# PAGE1.net
KiCad netlist of a schematic drawn in Altium Designer
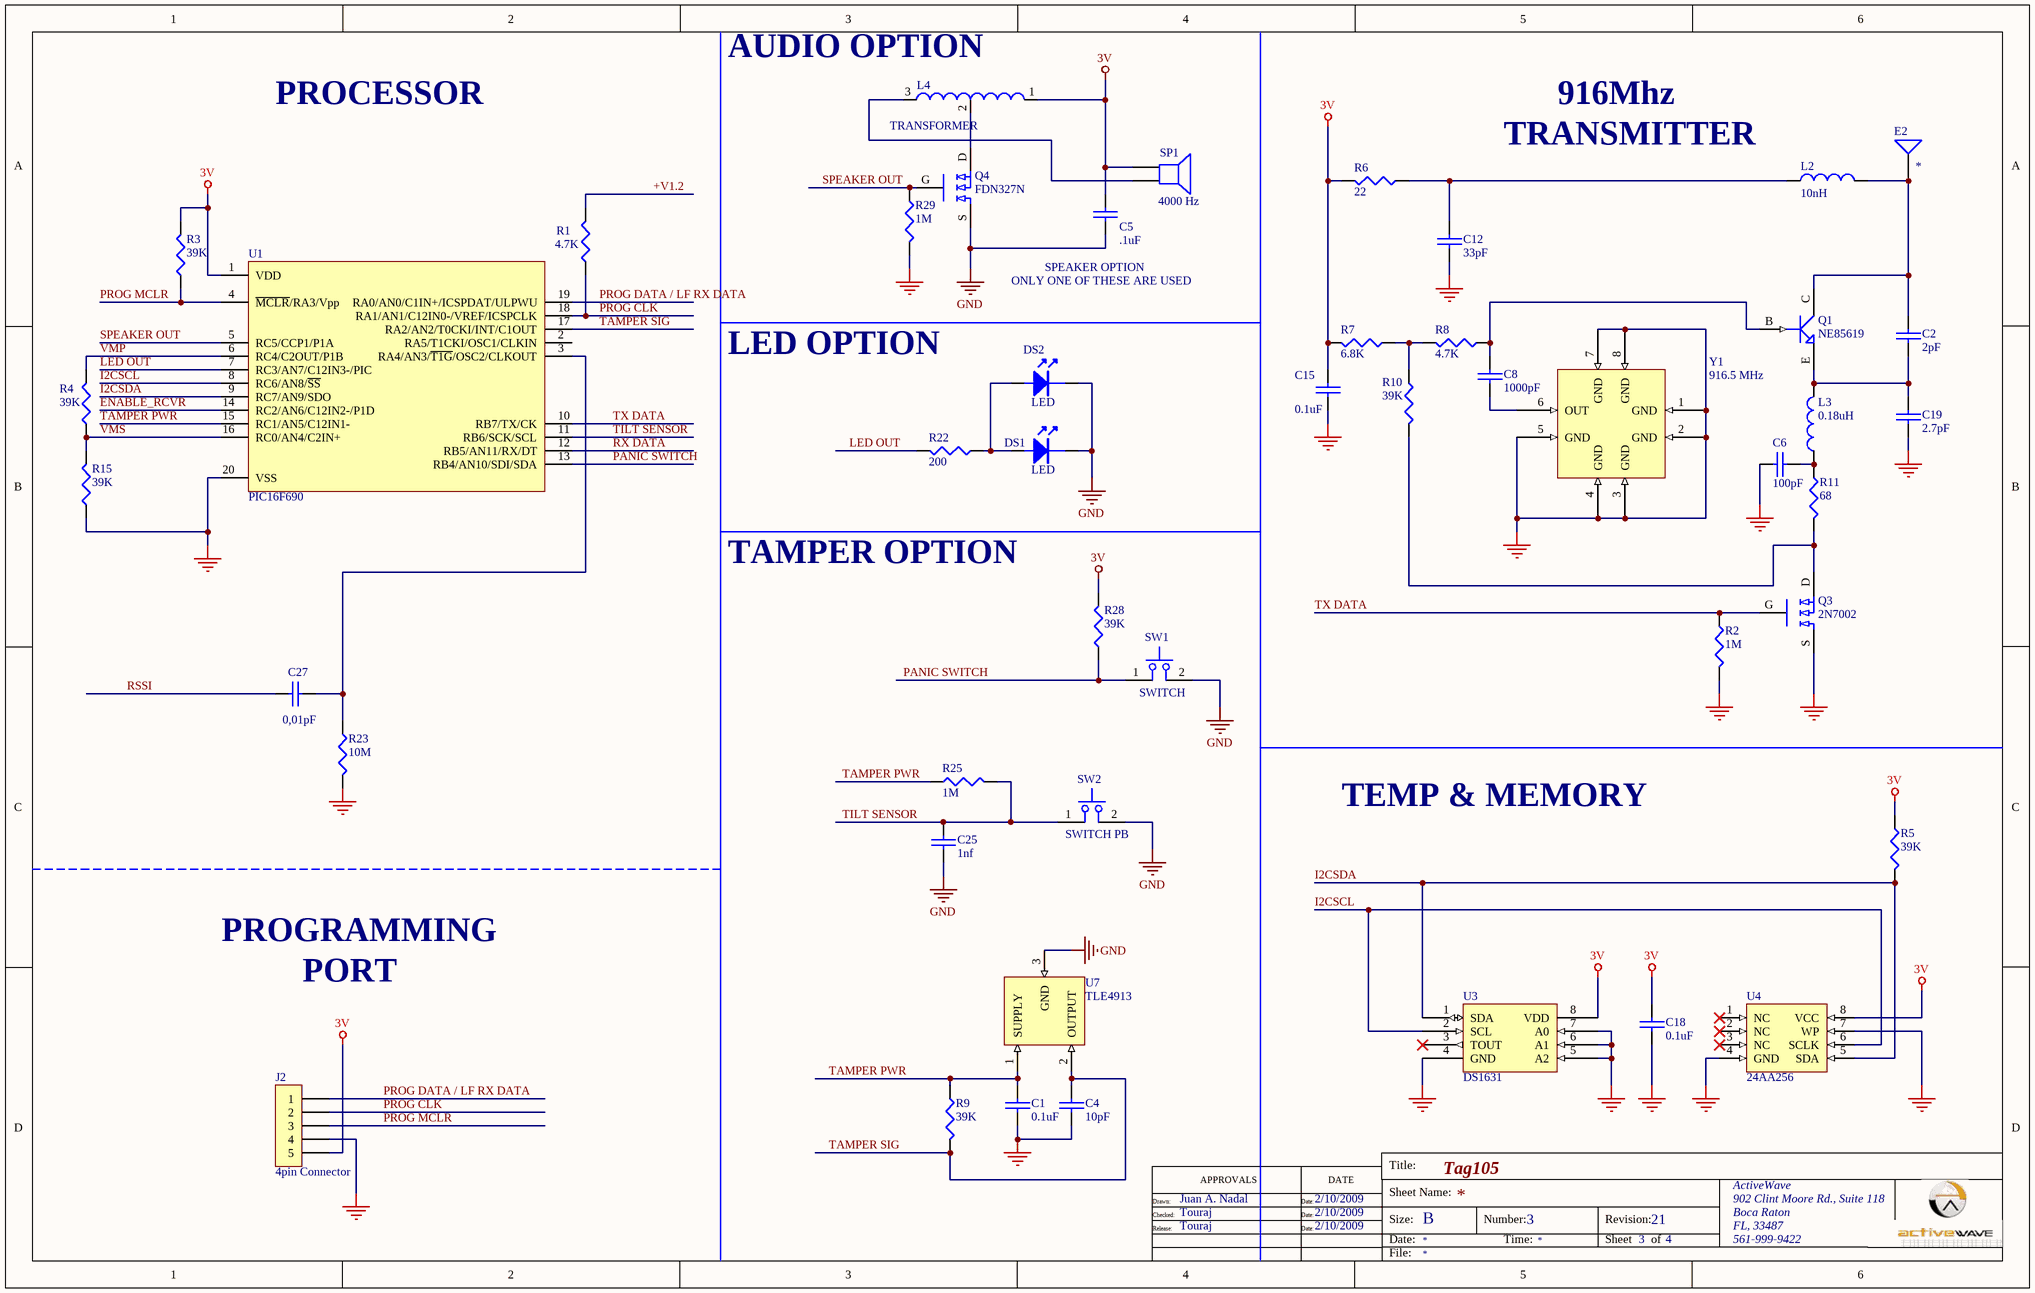
[diagram p0: PAGE1.schdoc]

(export (version "E")
  (design (tool "Eeschema 10.0.6"))
  (components
    (comp (ref "C1")
      (value "0.1uF")
      (footprint "0603")
      (description "Capacitor")
      (libsource (lib "ActiveWave MasterLib") (part "CAP-0603"))
    )
    (comp (ref "C2")
      (value "2pF")
      (footprint "0603")
      (description "Capacitor")
      (libsource (lib "ActiveWave MasterLib") (part "CAP-0603"))
    )
    (comp (ref "C4")
      (value "10pF")
      (footprint "0603")
      (description "Capacitor")
      (libsource (lib "ActiveWave MasterLib") (part "CAP-0603"))
    )
    (comp (ref "C5")
      (value ".1uF")
      (footprint "0603")
      (description "Capacitor")
      (libsource (lib "ActiveWave MasterLib") (part "CAP-0603"))
    )
    (comp (ref "C6")
      (value "100pF")
      (footprint "0603")
      (description "Capacitor")
      (libsource (lib "ActiveWave MasterLib") (part "CAP-0603"))
    )
    (comp (ref "C8")
      (value "1000pF")
      (footprint "0603")
      (description "Capacitor")
      (libsource (lib "ActiveWave MasterLib") (part "CAP-0603"))
    )
    (comp (ref "C12")
      (value "33pF")
      (footprint "0603")
      (description "Capacitor")
      (libsource (lib "ActiveWave MasterLib") (part "CAP-0603"))
    )
    (comp (ref "C15")
      (value "0.1uF")
      (footprint "0603")
      (description "Capacitor")
      (libsource (lib "ActiveWave MasterLib") (part "CAP-0603"))
    )
    (comp (ref "C18")
      (value "0.1uF")
      (footprint "0603")
      (description "Capacitor")
      (libsource (lib "ActiveWave MasterLib") (part "CAP-0603"))
    )
    (comp (ref "C19")
      (value "2.7pF")
      (footprint "0603")
      (description "Capacitor")
      (libsource (lib "ActiveWave MasterLib") (part "CAP-0603"))
    )
    (comp (ref "C25")
      (value "1nf")
      (footprint "0603")
      (description "Capacitor")
      (libsource (lib "ActiveWave MasterLib") (part "CAP-0603"))
    )
    (comp (ref "C27")
      (value "0,01pF")
      (footprint "0603")
      (description "Capacitor")
      (libsource (lib "ActiveWave MasterLib") (part "CAP-0603"))
    )
    (comp (ref "DS1")
      (value "LED")
      (footprint "404-1032-2-ND")
      (libsource (lib "ActiveWave MasterLib") (part "LED"))
    )
    (comp (ref "DS2")
      (value "LED")
      (footprint "LCE-358RP")
      (description "X-Bring Red Power SMD LED Emitter")
      (fields (field (name "MANUFACTURER") "L.C. LED"))
      (libsource (lib "ActiveWave MasterLib") (part "LCE-358RP"))
    )
    (comp (ref "E2")
      (value "*")
      (footprint "Antenna1")
      (fields (field (name "ALTIUM_VALUE") "*"))
      (libsource (lib "ActiveWave MasterLib") (part "Antenna1"))
    )
    (comp (ref "J2")
      (value "4pin Connector")
      (footprint "1X5 HEADER")
      (description "Connector")
      (libsource (lib "ActiveWave MasterLib") (part "CON5-1"))
    )
    (comp (ref "L2")
      (value "10nH")
      (footprint "0603")
      (libsource (lib "ActiveWave MasterLib") (part "INDUCTOR"))
    )
    (comp (ref "L3")
      (value "0.18uH")
      (footprint "0603")
      (libsource (lib "ActiveWave MasterLib") (part "INDUCTOR"))
    )
    (comp (ref "L4")
      (value "TRANSFORMER")
      (footprint "COIL_6mmx6mm_011012")
      (libsource (lib "ActiveWave MasterLib") (part "INDUCTOR_V2"))
    )
    (comp (ref "Q1")
      (value "NE85619")
      (footprint "3 PIN ULTRA SUPER MINI MOLD")
      (description "TRANSISTOR NPN 1GHZ SMD")
      (fields (field (name "MANUFACTURER") "??????"))
      (libsource (lib "ActiveWave MasterLib") (part "NE85619"))
    )
    (comp (ref "Q3")
      (value "2N7002")
      (footprint "SOT23 FET")
      (description "N-CHANNEL ENHANCEMENT MODE FIELD EFFECT TRANSISTOR")
      (fields (field (name "MANUFACTURER") "FAIRCHILD"))
      (libsource (lib "ActiveWave MasterLib") (part "2N7002"))
    )
    (comp (ref "Q4")
      (value "FDN327N")
      (footprint "SOT23 FET")
      (description "20V N-Channel MOSFET")
      (fields (field (name "MANUFACTURER") "FAIRCHILD"))
      (libsource (lib "ActiveWave MasterLib") (part "FDN327N"))
    )
    (comp (ref "R1") (value "4.7K") (footprint "0603") (libsource (lib "*") (part "RESISTOR")))
    (comp (ref "R2") (value "1M") (libsource (lib "ActiveWave MasterLib") (part "RES-0402")))
    (comp (ref "R3")
      (value "39K")
      (footprint "0603")
      (libsource (lib "ActiveWave MasterLib") (part "RES-0603"))
    )
    (comp (ref "R4")
      (value "39K")
      (footprint "0603")
      (libsource (lib "ActiveWave MasterLib") (part "RES-0603"))
    )
    (comp (ref "R5")
      (value "39K")
      (footprint "0603")
      (libsource (lib "ActiveWave MasterLib") (part "RES-0603"))
    )
    (comp (ref "R6") (value "22") (libsource (lib "ActiveWave MasterLib") (part "RES-0402")))
    (comp (ref "R7") (value "6.8K") (libsource (lib "ActiveWave MasterLib") (part "RES-0402")))
    (comp (ref "R8") (value "4.7K") (libsource (lib "ActiveWave MasterLib") (part "RES-0402")))
    (comp (ref "R9")
      (value "39K")
      (footprint "0603")
      (libsource (lib "ActiveWave MasterLib") (part "RES-0603"))
    )
    (comp (ref "R10")
      (value "39K")
      (footprint "0603")
      (libsource (lib "ActiveWave MasterLib") (part "RES-0603"))
    )
    (comp (ref "R11") (value "68") (libsource (lib "ActiveWave MasterLib") (part "RES-0402")))
    (comp (ref "R15")
      (value "39K")
      (footprint "0603")
      (libsource (lib "ActiveWave MasterLib") (part "RES-0603"))
    )
    (comp (ref "R22")
      (value "200")
      (footprint "0603")
      (libsource (lib "ActiveWave MasterLib") (part "RES-0603"))
    )
    (comp (ref "R23")
      (value "10M")
      (footprint "0603")
      (libsource (lib "ActiveWave MasterLib") (part "RES-0603"))
    )
    (comp (ref "R25")
      (value "1M")
      (footprint "0603")
      (libsource (lib "ActiveWave MasterLib") (part "RES-0603"))
    )
    (comp (ref "R28")
      (value "39K")
      (footprint "0603")
      (libsource (lib "ActiveWave MasterLib") (part "RES-0603"))
    )
    (comp (ref "R29")
      (value "1M")
      (footprint "0603")
      (libsource (lib "ActiveWave MasterLib") (part "RES-0402"))
    )
    (comp (ref "SP1")
      (value "4000 Hz")
      (footprint "SPEAKER 12mmx12mm_011012")
      (description "Surface Mount Transducer")
      (fields (field (name "MANUFACTURER") "PUI Audio"))
      (libsource (lib "ActiveWave MasterLib") (part "SMT-1028-S-R"))
    )
    (comp (ref "SW1")
      (value "SWITCH")
      (footprint "SWITCH PB REVERSED_082907")
      (libsource (lib "ActiveWave MasterLib") (part "SWITCH"))
    )
    (comp (ref "SW2")
      (value "SWITCH PB")
      (footprint "SQ-SEN-DUAL1")
      (libsource (lib "ActiveWave MasterLib") (part "SWITCH PB"))
    )
    (comp (ref "U1")
      (value "PIC16F690")
      (footprint "SSOP20 WIDE")
      (description "Microcontrollers (MCU) 7KB FL 256R 18 I/O")
      (fields (field (name "MANUFACTURER") "Microchip"))
      (libsource (lib "ActiveWave MasterLib") (part "PIC16F690-E/P"))
    )
    (comp (ref "U3")
      (value "DS1631")
      (footprint "SO8 SMALL")
      (description "High-Precision Digital Thermometer and Thermostat")
      (fields (field (name "MANUFACTURER") "DALLAS SEMICONDUCTOR"))
      (libsource (lib "ActiveWave MasterLib") (part "DS1631"))
    )
    (comp (ref "U4")
      (value "24AA256")
      (footprint "SO8")
      (description "24AA256 32k Microchip Serial EEPROM")
      (fields (field (name "MANUFACTURER") "Microchip"))
      (libsource (lib "ActiveWave MasterLib") (part "24AA256-I/P"))
    )
    (comp (ref "U7")
      (value "TLE4913")
      (footprint "SOT23W")
      (description "Low Power Hall Switch")
      (fields (field (name "MANUFACTURER") "Infineon Technologies AG"))
      (libsource (lib "ActiveWave MasterLib") (part "TLE4913"))
    )
    (comp (ref "Y1")
      (value "916.5 MHz")
      (footprint "RESONATOR")
      (description "916.5 MHz Saw Resonator")
      (fields (field (name "MANUFACTURER") "??????"))
      (libsource (lib "ActiveWave MasterLib") (part "RESONATOR"))
    )
  )
  (nets
    (net (code "1") (name "/+V1.2") (class "Default")
      (node (ref "R1") (pin "2") (pinfunction "2_2") (pintype "passive"))
    )
    (net (code "2") (name "/ENABLE_RCVR") (class "Default")
      (node (ref "U1") (pin "14") (pinfunction "RC2/AN6/C12IN2-/P1D_14") (pintype "passive"))
    )
    (net (code "3") (name "/I2CSCL") (class "Default")
      (node (ref "U1") (pin "8") (pinfunction "RC6/AN8/~{SS}_8") (pintype "passive"))
      (node (ref "U3") (pin "2") (pinfunction "SCL_2") (pintype "input"))
      (node (ref "U4") (pin "6") (pinfunction "SCLK_6") (pintype "input"))
    )
    (net (code "4") (name "/I2CSDA") (class "Default")
      (node (ref "R5") (pin "2") (pinfunction "2_2") (pintype "passive"))
      (node (ref "U1") (pin "9") (pinfunction "RC7/AN9/SDO_9") (pintype "passive"))
      (node (ref "U3") (pin "1") (pinfunction "SDA_1") (pintype "bidirectional"))
      (node (ref "U4") (pin "5") (pinfunction "SDA_5") (pintype "input"))
    )
    (net (code "5") (name "/LED OUT") (class "Default")
      (node (ref "R22") (pin "2") (pinfunction "2_2") (pintype "passive"))
      (node (ref "U1") (pin "7") (pinfunction "RC3/AN7/C12IN3-/PIC_7") (pintype "passive"))
    )
    (net (code "6") (name "/PANIC SWITCH") (class "Default")
      (node (ref "R28") (pin "1") (pinfunction "1_1") (pintype "passive"))
      (node (ref "SW1") (pin "1") (pinfunction "1_1") (pintype "passive"))
      (node (ref "U1") (pin "13") (pinfunction "RB4/AN10/SDI/SDA_13") (pintype "passive"))
    )
    (net (code "7") (name "/PROG CLK") (class "Default")
      (node (ref "J2") (pin "2") (pinfunction "2_2") (pintype "passive"))
      (node (ref "R1") (pin "1") (pinfunction "1_1") (pintype "passive"))
      (node (ref "U1") (pin "18") (pinfunction "RA1/AN1/C12IN0-/VREF/ICSPCLK_18") (pintype "passive"))
    )
    (net (code "8") (name "/PROG DATA {slash} LF RX DATA") (class "Default")
      (node (ref "J2") (pin "1") (pinfunction "1_1") (pintype "passive"))
      (node (ref "U1") (pin "19") (pinfunction "RA0/AN0/C1IN+/ICSPDAT/ULPWU_19") (pintype "passive"))
    )
    (net (code "9") (name "/PROG MCLR") (class "Default")
      (node (ref "J2") (pin "3") (pinfunction "3_3") (pintype "passive"))
      (node (ref "R3") (pin "1") (pinfunction "1_1") (pintype "passive"))
      (node (ref "U1") (pin "4") (pinfunction "~{MCLR}/RA3/Vpp_4") (pintype "passive"))
    )
    (net (code "10") (name "/RSSI") (class "Default")
      (node (ref "C27") (pin "1") (pinfunction "1_1") (pintype "passive"))
    )
    (net (code "11") (name "/RX DATA") (class "Default")
      (node (ref "U1") (pin "12") (pinfunction "RB5/AN11/RX/DT_12") (pintype "passive"))
    )
    (net (code "12") (name "/SPEAKER OUT") (class "Default")
      (node (ref "Q4") (pin "G") (pinfunction "G_G") (pintype "passive"))
      (node (ref "R29") (pin "1") (pinfunction "1_1") (pintype "passive"))
      (node (ref "U1") (pin "5") (pinfunction "RC5/CCP1/P1A_5") (pintype "passive"))
    )
    (net (code "13") (name "/TAMPER PWR") (class "Default")
      (node (ref "C1") (pin "1") (pinfunction "1_1") (pintype "passive"))
      (node (ref "R25") (pin "1") (pinfunction "1_1") (pintype "passive"))
      (node (ref "R9") (pin "1") (pinfunction "1_1") (pintype "passive"))
      (node (ref "U1") (pin "15") (pinfunction "RC1/AN5/C12IN1-_15") (pintype "passive"))
      (node (ref "U7") (pin "1") (pinfunction "SUPPLY_1") (pintype "input"))
    )
    (net (code "14") (name "/TAMPER SIG") (class "Default")
      (node (ref "C4") (pin "1") (pinfunction "1_1") (pintype "passive"))
      (node (ref "R9") (pin "2") (pinfunction "2_2") (pintype "passive"))
      (node (ref "U1") (pin "17") (pinfunction "RA2/AN2/T0CKI/INT/C1OUT_17") (pintype "passive"))
      (node (ref "U7") (pin "2") (pinfunction "OUTPUT_2") (pintype "input"))
    )
    (net (code "15") (name "/TILT SENSOR") (class "Default")
      (node (ref "C25") (pin "1") (pinfunction "1_1") (pintype "passive"))
      (node (ref "R25") (pin "2") (pinfunction "2_2") (pintype "passive"))
      (node (ref "SW2") (pin "1") (pinfunction "1_1") (pintype "passive"))
      (node (ref "U1") (pin "11") (pinfunction "RB6/SCK/SCL_11") (pintype "passive"))
    )
    (net (code "16") (name "/TX DATA") (class "Default")
      (node (ref "Q3") (pin "G") (pinfunction "G_G") (pintype "passive"))
      (node (ref "R2") (pin "1") (pinfunction "1_1") (pintype "passive"))
      (node (ref "U1") (pin "10") (pinfunction "RB7/TX/CK_10") (pintype "passive"))
    )
    (net (code "17") (name "/VMP") (class "Default")
      (node (ref "R4") (pin "2") (pinfunction "2_2") (pintype "passive"))
      (node (ref "U1") (pin "6") (pinfunction "RC4/C2OUT/P1B_6") (pintype "passive"))
    )
    (net (code "18") (name "/VMS") (class "Default")
      (node (ref "R15") (pin "2") (pinfunction "2_2") (pintype "passive"))
      (node (ref "R4") (pin "1") (pinfunction "1_1") (pintype "passive"))
      (node (ref "U1") (pin "16") (pinfunction "RC0/AN4/C2IN+_16") (pintype "passive"))
    )
    (net (code "19") (name "3V") (class "Default")
      (node (ref "C15") (pin "1") (pinfunction "1_1") (pintype "passive"))
      (node (ref "C18") (pin "1") (pinfunction "1_1") (pintype "passive"))
      (node (ref "C5") (pin "1") (pinfunction "1_1") (pintype "passive"))
      (node (ref "J2") (pin "5") (pinfunction "5_5") (pintype "passive"))
      (node (ref "L4") (pin "1") (pinfunction "1_1") (pintype "passive"))
      (node (ref "R28") (pin "2") (pinfunction "2_2") (pintype "passive"))
      (node (ref "R3") (pin "2") (pinfunction "2_2") (pintype "passive"))
      (node (ref "R5") (pin "1") (pinfunction "1_1") (pintype "passive"))
      (node (ref "R6") (pin "2") (pinfunction "2_2") (pintype "passive"))
      (node (ref "R7") (pin "2") (pinfunction "2_2") (pintype "passive"))
      (node (ref "SP1") (pin "1") (pinfunction "1_1") (pintype "passive"))
      (node (ref "U1") (pin "1") (pinfunction "VDD_1") (pintype "passive"))
      (node (ref "U3") (pin "8") (pinfunction "VDD_8") (pintype "power_in"))
      (node (ref "U4") (pin "8") (pinfunction "VCC_8") (pintype "input"))
    )
    (net (code "20") (name "GND") (class "Default")
      (node (ref "C1") (pin "2") (pinfunction "2_2") (pintype "passive"))
      (node (ref "C12") (pin "2") (pinfunction "2_2") (pintype "passive"))
      (node (ref "C15") (pin "2") (pinfunction "2_2") (pintype "passive"))
      (node (ref "C18") (pin "2") (pinfunction "2_2") (pintype "passive"))
      (node (ref "C19") (pin "2") (pinfunction "2_2") (pintype "passive"))
      (node (ref "C25") (pin "2") (pinfunction "2_2") (pintype "passive"))
      (node (ref "C4") (pin "2") (pinfunction "2_2") (pintype "passive"))
      (node (ref "C5") (pin "2") (pinfunction "2_2") (pintype "passive"))
      (node (ref "C6") (pin "2") (pinfunction "2_2") (pintype "passive"))
      (node (ref "DS1") (pin "K") (pinfunction "K_K") (pintype "passive"))
      (node (ref "DS2") (pin "2") (pinfunction "2_2") (pintype "passive"))
      (node (ref "J2") (pin "4") (pinfunction "4_4") (pintype "passive"))
      (node (ref "Q3") (pin "S") (pinfunction "S_S") (pintype "passive"))
      (node (ref "Q4") (pin "S") (pinfunction "S_S") (pintype "passive"))
      (node (ref "R15") (pin "1") (pinfunction "1_1") (pintype "passive"))
      (node (ref "R2") (pin "2") (pinfunction "2_2") (pintype "passive"))
      (node (ref "R23") (pin "2") (pinfunction "2_2") (pintype "passive"))
      (node (ref "R29") (pin "2") (pinfunction "2_2") (pintype "passive"))
      (node (ref "SW1") (pin "2") (pinfunction "2_2") (pintype "passive"))
      (node (ref "SW2") (pin "2") (pinfunction "2_2") (pintype "passive"))
      (node (ref "U1") (pin "20") (pinfunction "VSS_20") (pintype "passive"))
      (node (ref "U3") (pin "4") (pinfunction "GND_4") (pintype "power_in"))
      (node (ref "U3") (pin "5") (pinfunction "A2_5") (pintype "input"))
      (node (ref "U3") (pin "6") (pinfunction "A1_6") (pintype "input"))
      (node (ref "U3") (pin "7") (pinfunction "A0_7") (pintype "input"))
      (node (ref "U4") (pin "4") (pinfunction "GND_4") (pintype "input"))
      (node (ref "U4") (pin "7") (pinfunction "WP_7") (pintype "input"))
      (node (ref "U7") (pin "3") (pinfunction "GND_3") (pintype "input"))
      (node (ref "Y1") (pin "1") (pinfunction "GND_1") (pintype "input"))
      (node (ref "Y1") (pin "2") (pinfunction "GND_2") (pintype "input"))
      (node (ref "Y1") (pin "3") (pinfunction "GND_3") (pintype "input"))
      (node (ref "Y1") (pin "4") (pinfunction "GND_4") (pintype "input"))
      (node (ref "Y1") (pin "5") (pinfunction "GND_5") (pintype "input"))
      (node (ref "Y1") (pin "7") (pinfunction "GND_7") (pintype "input"))
      (node (ref "Y1") (pin "8") (pinfunction "GND_8") (pintype "input"))
    )
    (net (code "21") (name "Net-(C2-Pad1)") (class "Default")
      (node (ref "C2") (pin "1") (pinfunction "1_1") (pintype "passive"))
      (node (ref "E2") (pin "1") (pinfunction "1_1") (pintype "passive"))
      (node (ref "L2") (pin "2") (pinfunction "2_2") (pintype "passive"))
      (node (ref "Q1") (pin "C") (pinfunction "C_C") (pintype "passive"))
    )
    (net (code "22") (name "Net-(C6-Pad1)") (class "Default")
      (node (ref "C6") (pin "1") (pinfunction "1_1") (pintype "passive"))
      (node (ref "L3") (pin "1") (pinfunction "1_1") (pintype "passive"))
      (node (ref "R11") (pin "1") (pinfunction "1_1") (pintype "passive"))
    )
    (net (code "23") (name "Net-(C8-Pad1)") (class "Default")
      (node (ref "C8") (pin "1") (pinfunction "1_1") (pintype "passive"))
      (node (ref "Q1") (pin "B") (pinfunction "B_B") (pintype "input"))
      (node (ref "R8") (pin "1") (pinfunction "1_1") (pintype "passive"))
    )
    (net (code "24") (name "Net-(C12-Pad1)") (class "Default")
      (node (ref "C12") (pin "1") (pinfunction "1_1") (pintype "passive"))
      (node (ref "L2") (pin "1") (pinfunction "1_1") (pintype "passive"))
      (node (ref "R6") (pin "1") (pinfunction "1_1") (pintype "passive"))
    )
    (net (code "25") (name "Net-(C19-Pad1)") (class "Default")
      (node (ref "C19") (pin "1") (pinfunction "1_1") (pintype "passive"))
      (node (ref "C2") (pin "2") (pinfunction "2_2") (pintype "passive"))
      (node (ref "L3") (pin "2") (pinfunction "2_2") (pintype "passive"))
      (node (ref "Q1") (pin "E") (pinfunction "E_E") (pintype "passive"))
    )
    (net (code "26") (name "Net-(DS1-PadA)") (class "Default")
      (node (ref "DS1") (pin "A") (pinfunction "A_A") (pintype "passive"))
      (node (ref "DS2") (pin "1") (pinfunction "1_1") (pintype "passive"))
      (node (ref "R22") (pin "1") (pinfunction "1_1") (pintype "passive"))
    )
    (net (code "27") (name "Net-(L4-Pad2)") (class "Default")
      (node (ref "L4") (pin "2") (pinfunction "2_2") (pintype "passive"))
      (node (ref "Q4") (pin "D") (pinfunction "D_D") (pintype "passive"))
    )
    (net (code "28") (name "Net-(L4-Pad3)") (class "Default")
      (node (ref "L4") (pin "3") (pinfunction "3_3") (pintype "passive"))
      (node (ref "SP1") (pin "2") (pinfunction "2_2") (pintype "passive"))
    )
    (net (code "29") (name "Net-(Q3-PadD)") (class "Default")
      (node (ref "Q3") (pin "D") (pinfunction "D_D") (pintype "passive"))
      (node (ref "R10") (pin "2") (pinfunction "2_2") (pintype "passive"))
      (node (ref "R11") (pin "2") (pinfunction "2_2") (pintype "passive"))
    )
    (net (code "30") (name "Net-(R10-Pad1)") (class "Default")
      (node (ref "R10") (pin "1") (pinfunction "1_1") (pintype "passive"))
      (node (ref "R7") (pin "1") (pinfunction "1_1") (pintype "passive"))
      (node (ref "R8") (pin "2") (pinfunction "2_2") (pintype "passive"))
    )
    (net (code "31") (name "Net-(U1-RA4{slash}AN3{slash}~{T1G}{slash}OSC2{slash}CLKOUT)") (class "Default")
      (node (ref "C27") (pin "2") (pinfunction "2_2") (pintype "passive"))
      (node (ref "R23") (pin "1") (pinfunction "1_1") (pintype "passive"))
      (node (ref "U1") (pin "3") (pinfunction "RA4/AN3/~{T1G}/OSC2/CLKOUT_3") (pintype "passive"))
    )
    (net (code "32") (name "Net-(Y1-OUT)") (class "Default")
      (node (ref "C8") (pin "2") (pinfunction "2_2") (pintype "passive"))
      (node (ref "Y1") (pin "6") (pinfunction "OUT_6") (pintype "input"))
    )
    (net (code "33") (name "unconnected-(U1-RA5{slash}T1CKI{slash}OSC1{slash}CLKIN-Pad2)") (class "Default")
      (node (ref "U1") (pin "2") (pinfunction "RA5/T1CKI/OSC1/CLKIN_2") (pintype "passive"))
    )
    (net (code "34") (name "unconnected-(U3-TOUT-Pad3)") (class "Default")
      (node (ref "U3") (pin "3") (pinfunction "TOUT_3") (pintype "output+no_connect"))
    )
    (net (code "35") (name "unconnected-(U4-NC-Pad1)") (class "Default")
      (node (ref "U4") (pin "1") (pinfunction "NC_1") (pintype "input+no_connect"))
    )
    (net (code "36") (name "unconnected-(U4-NC-Pad2)") (class "Default")
      (node (ref "U4") (pin "2") (pinfunction "NC_2") (pintype "input+no_connect"))
    )
    (net (code "37") (name "unconnected-(U4-NC-Pad3)") (class "Default")
      (node (ref "U4") (pin "3") (pinfunction "NC_3") (pintype "input+no_connect"))
    )
  )
)
